# 44_GE_PORT_1-2.net
KiCad netlist of a schematic drawn in Altium Designer
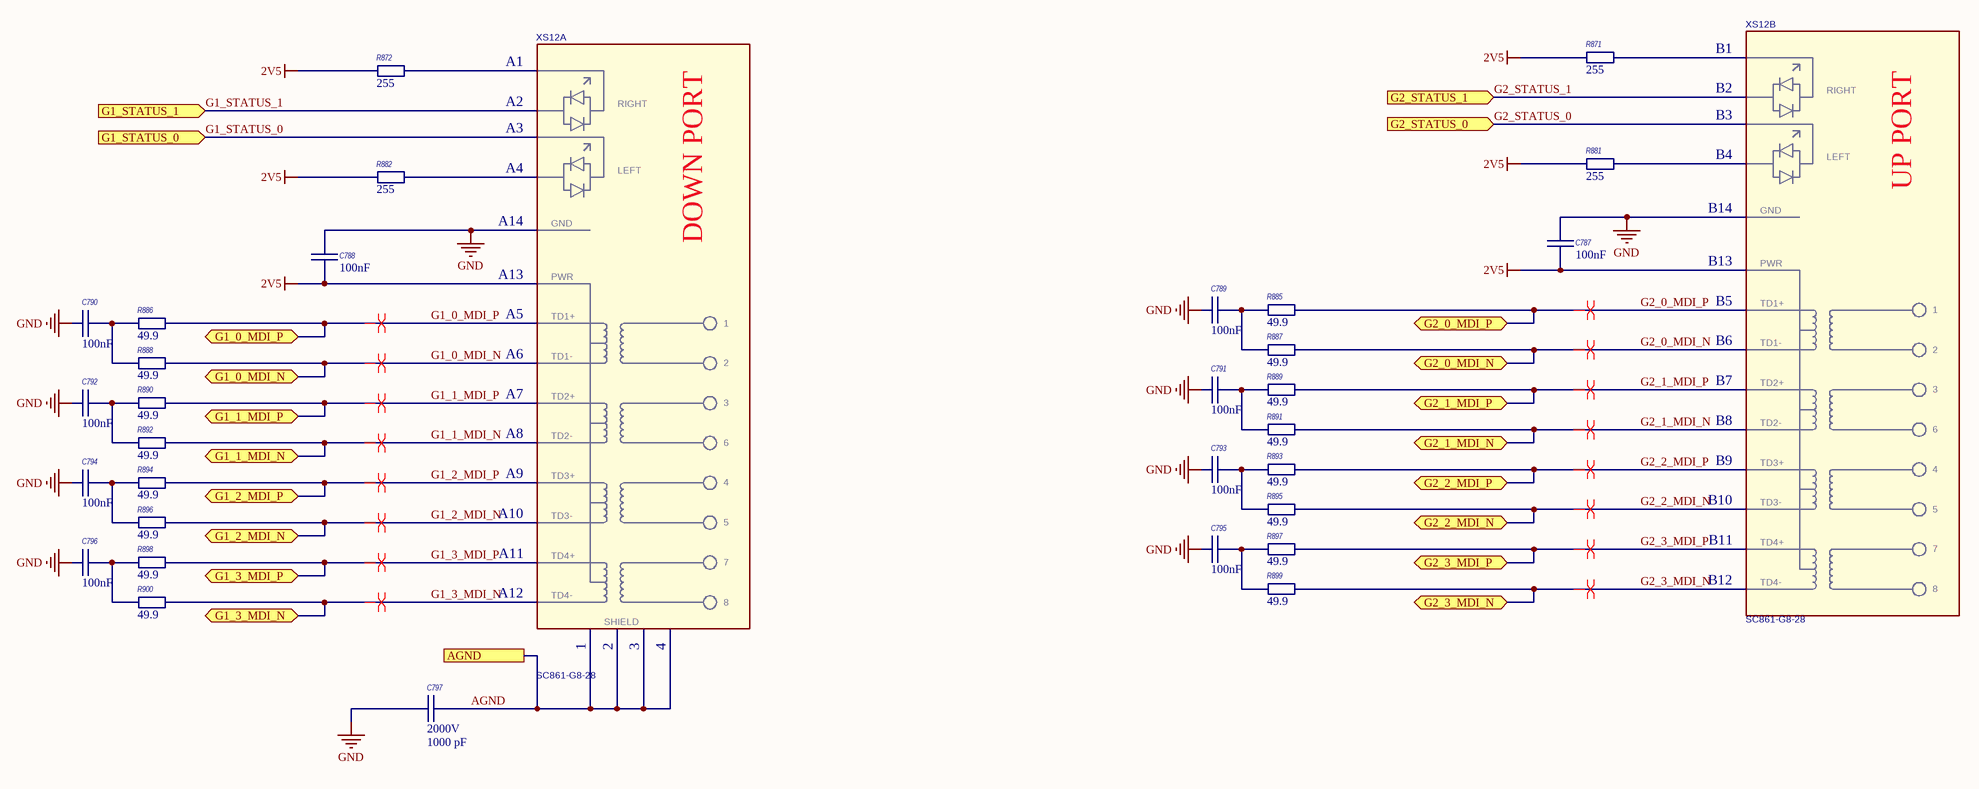
[diagram p0: 44_GE_PORT_1-2.SchDoc]

(export (version "E")
  (design (tool "Eeschema 10.0.6"))
  (components
    (comp (ref "C787")
      (value "GRM155R71E104KE14D")
      (footprint "C0402_IPC High Density")
      (description "C0402, 100nF, 25V, X7R")
      (fields
        (field (name "MANUFACTURER") "Murata")
        (field (name "CAPACITANCE") "100nF")
        (field (name "CUSTOMER PART NUMBER") "Конденсатор, 100n, 0402, 25V, X7R, 10%")
      )
      (libsource (lib "CAPACITORS") (part "GRM155R71E104KE14D"))
    )
    (comp (ref "C788")
      (value "GRM155R71E104KE14D")
      (footprint "C0402_IPC High Density")
      (description "C0402, 100nF, 25V, X7R")
      (fields
        (field (name "MANUFACTURER") "Murata")
        (field (name "CAPACITANCE") "100nF")
        (field (name "CUSTOMER PART NUMBER") "Конденсатор, 100n, 0402, 25V, X7R, 10%")
      )
      (libsource (lib "CAPACITORS") (part "GRM155R71E104KE14D"))
    )
    (comp (ref "C789")
      (value "GRM155R71E104KE14D")
      (footprint "C0402_IPC High Density")
      (description "C0402, 100nF, 25V, X7R")
      (fields
        (field (name "MANUFACTURER") "Murata")
        (field (name "CAPACITANCE") "100nF")
        (field (name "CUSTOMER PART NUMBER") "Конденсатор, 100n, 0402, 25V, X7R, 10%")
      )
      (libsource (lib "CAPACITORS") (part "GRM155R71E104KE14D"))
    )
    (comp (ref "C790")
      (value "GRM155R71E104KE14D")
      (footprint "C0402_IPC High Density")
      (description "C0402, 100nF, 25V, X7R")
      (fields
        (field (name "MANUFACTURER") "Murata")
        (field (name "CAPACITANCE") "100nF")
        (field (name "CUSTOMER PART NUMBER") "Конденсатор, 100n, 0402, 25V, X7R, 10%")
      )
      (libsource (lib "CAPACITORS") (part "GRM155R71E104KE14D"))
    )
    (comp (ref "C791")
      (value "GRM155R71E104KE14D")
      (footprint "C0402_IPC High Density")
      (description "C0402, 100nF, 25V, X7R")
      (fields
        (field (name "MANUFACTURER") "Murata")
        (field (name "CAPACITANCE") "100nF")
        (field (name "CUSTOMER PART NUMBER") "Конденсатор, 100n, 0402, 25V, X7R, 10%")
      )
      (libsource (lib "CAPACITORS") (part "GRM155R71E104KE14D"))
    )
    (comp (ref "C792")
      (value "GRM155R71E104KE14D")
      (footprint "C0402_IPC High Density")
      (description "C0402, 100nF, 25V, X7R")
      (fields
        (field (name "MANUFACTURER") "Murata")
        (field (name "CAPACITANCE") "100nF")
        (field (name "CUSTOMER PART NUMBER") "Конденсатор, 100n, 0402, 25V, X7R, 10%")
      )
      (libsource (lib "CAPACITORS") (part "GRM155R71E104KE14D"))
    )
    (comp (ref "C793")
      (value "GRM155R71E104KE14D")
      (footprint "C0402_IPC High Density")
      (description "C0402, 100nF, 25V, X7R")
      (fields
        (field (name "MANUFACTURER") "Murata")
        (field (name "CAPACITANCE") "100nF")
        (field (name "CUSTOMER PART NUMBER") "Конденсатор, 100n, 0402, 25V, X7R, 10%")
      )
      (libsource (lib "CAPACITORS") (part "GRM155R71E104KE14D"))
    )
    (comp (ref "C794")
      (value "GRM155R71E104KE14D")
      (footprint "C0402_IPC High Density")
      (description "C0402, 100nF, 25V, X7R")
      (fields
        (field (name "MANUFACTURER") "Murata")
        (field (name "CAPACITANCE") "100nF")
        (field (name "CUSTOMER PART NUMBER") "Конденсатор, 100n, 0402, 25V, X7R, 10%")
      )
      (libsource (lib "CAPACITORS") (part "GRM155R71E104KE14D"))
    )
    (comp (ref "C795")
      (value "GRM155R71E104KE14D")
      (footprint "C0402_IPC High Density")
      (description "C0402, 100nF, 25V, X7R")
      (fields
        (field (name "MANUFACTURER") "Murata")
        (field (name "CAPACITANCE") "100nF")
        (field (name "CUSTOMER PART NUMBER") "Конденсатор, 100n, 0402, 25V, X7R, 10%")
      )
      (libsource (lib "CAPACITORS") (part "GRM155R71E104KE14D"))
    )
    (comp (ref "C796")
      (value "GRM155R71E104KE14D")
      (footprint "C0402_IPC High Density")
      (description "C0402, 100nF, 25V, X7R")
      (fields
        (field (name "MANUFACTURER") "Murata")
        (field (name "CAPACITANCE") "100nF")
        (field (name "CUSTOMER PART NUMBER") "Конденсатор, 100n, 0402, 25V, X7R, 10%")
      )
      (libsource (lib "CAPACITORS") (part "GRM155R71E104KE14D"))
    )
    (comp (ref "C797")
      (value "GR442QR73D102KW01L")
      (footprint "C1808")
      (description "C1808, 2KV 1000pF, X7R")
      (fields
        (field (name "MANUFACTURER") "Murata")
        (field (name "TOLERANCE") "10 %")
        (field (name "VOLTAGE RATING") "2000V")
        (field (name "CAPACITANCE") "1000 pF")
      )
      (libsource (lib "CAPACITORS") (part "GR442QR73D102KW01L"))
    )
    (comp (ref "R871")
      (value "ERJ-2RKF2550X")
      (footprint "RESC1005[0402]")
      (description "R0402, 255R 1%")
      (fields
        (field (name "MANUFACTURER") "Panasonic")
        (field (name "TOLERANCE") "±1%")
        (field (name "RESISTANCE (OHMS)") "255")
      )
      (libsource (lib "RESISTOR") (part "ERJ-2RKF2550X"))
    )
    (comp (ref "R872")
      (value "ERJ-2RKF2550X")
      (footprint "RESC1005[0402]")
      (description "R0402, 255R 1%")
      (fields
        (field (name "MANUFACTURER") "Panasonic")
        (field (name "TOLERANCE") "±1%")
        (field (name "RESISTANCE (OHMS)") "255")
      )
      (libsource (lib "RESISTOR") (part "ERJ-2RKF2550X"))
    )
    (comp (ref "R881")
      (value "ERJ-2RKF2550X")
      (footprint "RESC1005[0402]")
      (description "R0402, 255R 1%")
      (fields
        (field (name "MANUFACTURER") "Panasonic")
        (field (name "TOLERANCE") "±1%")
        (field (name "RESISTANCE (OHMS)") "255")
      )
      (libsource (lib "RESISTOR") (part "ERJ-2RKF2550X"))
    )
    (comp (ref "R882")
      (value "ERJ-2RKF2550X")
      (footprint "RESC1005[0402]")
      (description "R0402, 255R 1%")
      (fields
        (field (name "MANUFACTURER") "Panasonic")
        (field (name "TOLERANCE") "±1%")
        (field (name "RESISTANCE (OHMS)") "255")
      )
      (libsource (lib "RESISTOR") (part "ERJ-2RKF2550X"))
    )
    (comp (ref "R885")
      (value "ERJ-2RKF49R9X")
      (footprint "R0402_IPC High Density")
      (description "R0402, 49.9R 1%")
      (fields
        (field (name "MANUFACTURER") "Panasonic")
        (field (name "TOLERANCE") "1 %")
        (field (name "RESISTANCE") "49.9")
      )
      (libsource (lib "RESISTOR") (part "ERJ-2RKF49R9X"))
    )
    (comp (ref "R886")
      (value "ERJ-2RKF49R9X")
      (footprint "R0402_IPC High Density")
      (description "R0402, 49.9R 1%")
      (fields
        (field (name "MANUFACTURER") "Panasonic")
        (field (name "TOLERANCE") "1 %")
        (field (name "RESISTANCE") "49.9")
      )
      (libsource (lib "RESISTOR") (part "ERJ-2RKF49R9X"))
    )
    (comp (ref "R887")
      (value "ERJ-2RKF49R9X")
      (footprint "R0402_IPC High Density")
      (description "R0402, 49.9R 1%")
      (fields
        (field (name "MANUFACTURER") "Panasonic")
        (field (name "TOLERANCE") "1 %")
        (field (name "RESISTANCE") "49.9")
      )
      (libsource (lib "RESISTOR") (part "ERJ-2RKF49R9X"))
    )
    (comp (ref "R888")
      (value "ERJ-2RKF49R9X")
      (footprint "R0402_IPC High Density")
      (description "R0402, 49.9R 1%")
      (fields
        (field (name "MANUFACTURER") "Panasonic")
        (field (name "TOLERANCE") "1 %")
        (field (name "RESISTANCE") "49.9")
      )
      (libsource (lib "RESISTOR") (part "ERJ-2RKF49R9X"))
    )
    (comp (ref "R889")
      (value "ERJ-2RKF49R9X")
      (footprint "R0402_IPC High Density")
      (description "R0402, 49.9R 1%")
      (fields
        (field (name "MANUFACTURER") "Panasonic")
        (field (name "TOLERANCE") "1 %")
        (field (name "RESISTANCE") "49.9")
      )
      (libsource (lib "RESISTOR") (part "ERJ-2RKF49R9X"))
    )
    (comp (ref "R890")
      (value "ERJ-2RKF49R9X")
      (footprint "R0402_IPC High Density")
      (description "R0402, 49.9R 1%")
      (fields
        (field (name "MANUFACTURER") "Panasonic")
        (field (name "TOLERANCE") "1 %")
        (field (name "RESISTANCE") "49.9")
      )
      (libsource (lib "RESISTOR") (part "ERJ-2RKF49R9X"))
    )
    (comp (ref "R891")
      (value "ERJ-2RKF49R9X")
      (footprint "R0402_IPC High Density")
      (description "R0402, 49.9R 1%")
      (fields
        (field (name "MANUFACTURER") "Panasonic")
        (field (name "TOLERANCE") "1 %")
        (field (name "RESISTANCE") "49.9")
      )
      (libsource (lib "RESISTOR") (part "ERJ-2RKF49R9X"))
    )
    (comp (ref "R892")
      (value "ERJ-2RKF49R9X")
      (footprint "R0402_IPC High Density")
      (description "R0402, 49.9R 1%")
      (fields
        (field (name "MANUFACTURER") "Panasonic")
        (field (name "TOLERANCE") "1 %")
        (field (name "RESISTANCE") "49.9")
      )
      (libsource (lib "RESISTOR") (part "ERJ-2RKF49R9X"))
    )
    (comp (ref "R893")
      (value "ERJ-2RKF49R9X")
      (footprint "R0402_IPC High Density")
      (description "R0402, 49.9R 1%")
      (fields
        (field (name "MANUFACTURER") "Panasonic")
        (field (name "TOLERANCE") "1 %")
        (field (name "RESISTANCE") "49.9")
      )
      (libsource (lib "RESISTOR") (part "ERJ-2RKF49R9X"))
    )
    (comp (ref "R894")
      (value "ERJ-2RKF49R9X")
      (footprint "R0402_IPC High Density")
      (description "R0402, 49.9R 1%")
      (fields
        (field (name "MANUFACTURER") "Panasonic")
        (field (name "TOLERANCE") "1 %")
        (field (name "RESISTANCE") "49.9")
      )
      (libsource (lib "RESISTOR") (part "ERJ-2RKF49R9X"))
    )
    (comp (ref "R895")
      (value "ERJ-2RKF49R9X")
      (footprint "R0402_IPC High Density")
      (description "R0402, 49.9R 1%")
      (fields
        (field (name "MANUFACTURER") "Panasonic")
        (field (name "TOLERANCE") "1 %")
        (field (name "RESISTANCE") "49.9")
      )
      (libsource (lib "RESISTOR") (part "ERJ-2RKF49R9X"))
    )
    (comp (ref "R896")
      (value "ERJ-2RKF49R9X")
      (footprint "R0402_IPC High Density")
      (description "R0402, 49.9R 1%")
      (fields
        (field (name "MANUFACTURER") "Panasonic")
        (field (name "TOLERANCE") "1 %")
        (field (name "RESISTANCE") "49.9")
      )
      (libsource (lib "RESISTOR") (part "ERJ-2RKF49R9X"))
    )
    (comp (ref "R897")
      (value "ERJ-2RKF49R9X")
      (footprint "R0402_IPC High Density")
      (description "R0402, 49.9R 1%")
      (fields
        (field (name "MANUFACTURER") "Panasonic")
        (field (name "TOLERANCE") "1 %")
        (field (name "RESISTANCE") "49.9")
      )
      (libsource (lib "RESISTOR") (part "ERJ-2RKF49R9X"))
    )
    (comp (ref "R898")
      (value "ERJ-2RKF49R9X")
      (footprint "R0402_IPC High Density")
      (description "R0402, 49.9R 1%")
      (fields
        (field (name "MANUFACTURER") "Panasonic")
        (field (name "TOLERANCE") "1 %")
        (field (name "RESISTANCE") "49.9")
      )
      (libsource (lib "RESISTOR") (part "ERJ-2RKF49R9X"))
    )
    (comp (ref "R899")
      (value "ERJ-2RKF49R9X")
      (footprint "R0402_IPC High Density")
      (description "R0402, 49.9R 1%")
      (fields
        (field (name "MANUFACTURER") "Panasonic")
        (field (name "TOLERANCE") "1 %")
        (field (name "RESISTANCE") "49.9")
      )
      (libsource (lib "RESISTOR") (part "ERJ-2RKF49R9X"))
    )
    (comp (ref "R900")
      (value "ERJ-2RKF49R9X")
      (footprint "R0402_IPC High Density")
      (description "R0402, 49.9R 1%")
      (fields
        (field (name "MANUFACTURER") "Panasonic")
        (field (name "TOLERANCE") "1 %")
        (field (name "RESISTANCE") "49.9")
      )
      (libsource (lib "RESISTOR") (part "ERJ-2RKF49R9X"))
    )
    (comp (ref "XS12")
      (value "SC861-G8-28")
      (footprint "SC861-G8-28")
      (description "Connector RJ45 1G 2 ports (2*1) and LED")
      (fields
        (field (name "CUSTOMER PART NUMBER") "Разъем, SC861-G8-28, Connector RJ45 1G 2 ports (2*1) and LED")
        (field (name "MANUFACTURER") "Yueqing Shichuang Electronics")
      )
      (libsource (lib "CONNECTORS") (part "SC861-G8-28"))
    )
  )
  (nets
    (net (code "1") (name "/AGND") (class "Default")
      (node (ref "C797") (pin "2") (pintype "passive"))
      (node (ref "XS12") (pin "1") (pintype "passive"))
      (node (ref "XS12") (pin "2") (pintype "passive"))
      (node (ref "XS12") (pin "3") (pintype "passive"))
      (node (ref "XS12") (pin "4") (pintype "passive"))
    )
    (net (code "2") (name "/G1_0_MDI_N") (class "Default")
      (node (ref "R888") (pin "2") (pintype "passive"))
      (node (ref "XS12") (pin "A6") (pintype "passive"))
    )
    (net (code "3") (name "/G1_0_MDI_P") (class "Default")
      (node (ref "R886") (pin "2") (pintype "passive"))
      (node (ref "XS12") (pin "A5") (pintype "passive"))
    )
    (net (code "4") (name "/G1_1_MDI_N") (class "Default")
      (node (ref "R892") (pin "2") (pintype "passive"))
      (node (ref "XS12") (pin "A8") (pintype "passive"))
    )
    (net (code "5") (name "/G1_1_MDI_P") (class "Default")
      (node (ref "R890") (pin "2") (pintype "passive"))
      (node (ref "XS12") (pin "A7") (pintype "passive"))
    )
    (net (code "6") (name "/G1_2_MDI_N") (class "Default")
      (node (ref "R896") (pin "2") (pintype "passive"))
      (node (ref "XS12") (pin "A10") (pintype "passive"))
    )
    (net (code "7") (name "/G1_2_MDI_P") (class "Default")
      (node (ref "R894") (pin "2") (pintype "passive"))
      (node (ref "XS12") (pin "A9") (pintype "passive"))
    )
    (net (code "8") (name "/G1_3_MDI_N") (class "Default")
      (node (ref "R900") (pin "2") (pintype "passive"))
      (node (ref "XS12") (pin "A12") (pintype "passive"))
    )
    (net (code "9") (name "/G1_3_MDI_P") (class "Default")
      (node (ref "R898") (pin "2") (pintype "passive"))
      (node (ref "XS12") (pin "A11") (pintype "passive"))
    )
    (net (code "10") (name "/G1_STATUS_0") (class "Default")
      (node (ref "XS12") (pin "A3") (pintype "passive"))
    )
    (net (code "11") (name "/G1_STATUS_1") (class "Default")
      (node (ref "XS12") (pin "A2") (pintype "passive"))
    )
    (net (code "12") (name "/G2_0_MDI_N") (class "Default")
      (node (ref "R887") (pin "2") (pintype "passive"))
      (node (ref "XS12") (pin "B6") (pintype "passive"))
    )
    (net (code "13") (name "/G2_0_MDI_P") (class "Default")
      (node (ref "R885") (pin "2") (pintype "passive"))
      (node (ref "XS12") (pin "B5") (pintype "passive"))
    )
    (net (code "14") (name "/G2_1_MDI_N") (class "Default")
      (node (ref "R891") (pin "2") (pintype "passive"))
      (node (ref "XS12") (pin "B8") (pintype "passive"))
    )
    (net (code "15") (name "/G2_1_MDI_P") (class "Default")
      (node (ref "R889") (pin "2") (pintype "passive"))
      (node (ref "XS12") (pin "B7") (pintype "passive"))
    )
    (net (code "16") (name "/G2_2_MDI_N") (class "Default")
      (node (ref "R895") (pin "2") (pintype "passive"))
      (node (ref "XS12") (pin "B10") (pintype "passive"))
    )
    (net (code "17") (name "/G2_2_MDI_P") (class "Default")
      (node (ref "R893") (pin "2") (pintype "passive"))
      (node (ref "XS12") (pin "B9") (pintype "passive"))
    )
    (net (code "18") (name "/G2_3_MDI_N") (class "Default")
      (node (ref "R899") (pin "2") (pintype "passive"))
      (node (ref "XS12") (pin "B12") (pintype "passive"))
    )
    (net (code "19") (name "/G2_3_MDI_P") (class "Default")
      (node (ref "R897") (pin "2") (pintype "passive"))
      (node (ref "XS12") (pin "B11") (pintype "passive"))
    )
    (net (code "20") (name "/G2_STATUS_0") (class "Default")
      (node (ref "XS12") (pin "B3") (pintype "passive"))
    )
    (net (code "21") (name "/G2_STATUS_1") (class "Default")
      (node (ref "XS12") (pin "B2") (pintype "passive"))
    )
    (net (code "22") (name "2V5") (class "Default")
      (node (ref "C787") (pin "2") (pintype "passive"))
      (node (ref "C788") (pin "2") (pintype "passive"))
      (node (ref "R871") (pin "1") (pintype "passive"))
      (node (ref "R872") (pin "1") (pintype "passive"))
      (node (ref "R881") (pin "1") (pintype "passive"))
      (node (ref "R882") (pin "1") (pintype "passive"))
      (node (ref "XS12") (pin "A13") (pintype "passive"))
      (node (ref "XS12") (pin "B13") (pintype "passive"))
    )
    (net (code "23") (name "GND") (class "Default")
      (node (ref "C787") (pin "1") (pintype "passive"))
      (node (ref "C788") (pin "1") (pintype "passive"))
      (node (ref "C789") (pin "1") (pintype "passive"))
      (node (ref "C790") (pin "1") (pintype "passive"))
      (node (ref "C791") (pin "1") (pintype "passive"))
      (node (ref "C792") (pin "1") (pintype "passive"))
      (node (ref "C793") (pin "1") (pintype "passive"))
      (node (ref "C794") (pin "1") (pintype "passive"))
      (node (ref "C795") (pin "1") (pintype "passive"))
      (node (ref "C796") (pin "1") (pintype "passive"))
      (node (ref "C797") (pin "1") (pintype "passive"))
      (node (ref "XS12") (pin "A14") (pintype "passive"))
      (node (ref "XS12") (pin "B14") (pintype "passive"))
    )
    (net (code "24") (name "Net-(C789-Pad2)") (class "Default")
      (node (ref "C789") (pin "2") (pintype "passive"))
      (node (ref "R885") (pin "1") (pintype "passive"))
      (node (ref "R887") (pin "1") (pintype "passive"))
    )
    (net (code "25") (name "Net-(C790-Pad2)") (class "Default")
      (node (ref "C790") (pin "2") (pintype "passive"))
      (node (ref "R886") (pin "1") (pintype "passive"))
      (node (ref "R888") (pin "1") (pintype "passive"))
    )
    (net (code "26") (name "Net-(C791-Pad2)") (class "Default")
      (node (ref "C791") (pin "2") (pintype "passive"))
      (node (ref "R889") (pin "1") (pintype "passive"))
      (node (ref "R891") (pin "1") (pintype "passive"))
    )
    (net (code "27") (name "Net-(C792-Pad2)") (class "Default")
      (node (ref "C792") (pin "2") (pintype "passive"))
      (node (ref "R890") (pin "1") (pintype "passive"))
      (node (ref "R892") (pin "1") (pintype "passive"))
    )
    (net (code "28") (name "Net-(C793-Pad2)") (class "Default")
      (node (ref "C793") (pin "2") (pintype "passive"))
      (node (ref "R893") (pin "1") (pintype "passive"))
      (node (ref "R895") (pin "1") (pintype "passive"))
    )
    (net (code "29") (name "Net-(C794-Pad2)") (class "Default")
      (node (ref "C794") (pin "2") (pintype "passive"))
      (node (ref "R894") (pin "1") (pintype "passive"))
      (node (ref "R896") (pin "1") (pintype "passive"))
    )
    (net (code "30") (name "Net-(C795-Pad2)") (class "Default")
      (node (ref "C795") (pin "2") (pintype "passive"))
      (node (ref "R897") (pin "1") (pintype "passive"))
      (node (ref "R899") (pin "1") (pintype "passive"))
    )
    (net (code "31") (name "Net-(C796-Pad2)") (class "Default")
      (node (ref "C796") (pin "2") (pintype "passive"))
      (node (ref "R898") (pin "1") (pintype "passive"))
      (node (ref "R900") (pin "1") (pintype "passive"))
    )
    (net (code "32") (name "Net-(R871-Pad2)") (class "Default")
      (node (ref "R871") (pin "2") (pintype "passive"))
      (node (ref "XS12") (pin "B1") (pintype "passive"))
    )
    (net (code "33") (name "Net-(R872-Pad2)") (class "Default")
      (node (ref "R872") (pin "2") (pintype "passive"))
      (node (ref "XS12") (pin "A1") (pintype "passive"))
    )
    (net (code "34") (name "Net-(R881-Pad2)") (class "Default")
      (node (ref "R881") (pin "2") (pintype "passive"))
      (node (ref "XS12") (pin "B4") (pintype "passive"))
    )
    (net (code "35") (name "Net-(R882-Pad2)") (class "Default")
      (node (ref "R882") (pin "2") (pintype "passive"))
      (node (ref "XS12") (pin "A4") (pintype "passive"))
    )
    (net (code "36") (name "unconnected-(XS12-Pad113)") (class "Default")
      (node (ref "XS12") (pin "113") (pintype "passive"))
    )
    (net (code "37") (name "unconnected-(XS12-Pad113)_1") (class "Default")
      (node (ref "XS12") (pin "113") (pintype "passive"))
    )
    (net (code "38") (name "unconnected-(XS12-Pad114)") (class "Default")
      (node (ref "XS12") (pin "114") (pintype "passive"))
    )
    (net (code "39") (name "unconnected-(XS12-Pad114)_1") (class "Default")
      (node (ref "XS12") (pin "114") (pintype "passive"))
    )
    (net (code "40") (name "unconnected-(XS12-Pad115)") (class "Default")
      (node (ref "XS12") (pin "115") (pintype "passive"))
    )
    (net (code "41") (name "unconnected-(XS12-Pad115)_1") (class "Default")
      (node (ref "XS12") (pin "115") (pintype "passive"))
    )
    (net (code "42") (name "unconnected-(XS12-Pad116)") (class "Default")
      (node (ref "XS12") (pin "116") (pintype "passive"))
    )
    (net (code "43") (name "unconnected-(XS12-Pad116)_1") (class "Default")
      (node (ref "XS12") (pin "116") (pintype "passive"))
    )
    (net (code "44") (name "unconnected-(XS12-Pad117)") (class "Default")
      (node (ref "XS12") (pin "117") (pintype "passive"))
    )
    (net (code "45") (name "unconnected-(XS12-Pad117)_1") (class "Default")
      (node (ref "XS12") (pin "117") (pintype "passive"))
    )
    (net (code "46") (name "unconnected-(XS12-Pad118)") (class "Default")
      (node (ref "XS12") (pin "118") (pintype "passive"))
    )
    (net (code "47") (name "unconnected-(XS12-Pad118)_1") (class "Default")
      (node (ref "XS12") (pin "118") (pintype "passive"))
    )
    (net (code "48") (name "unconnected-(XS12-Pad119)") (class "Default")
      (node (ref "XS12") (pin "119") (pintype "passive"))
    )
    (net (code "49") (name "unconnected-(XS12-Pad119)_1") (class "Default")
      (node (ref "XS12") (pin "119") (pintype "passive"))
    )
    (net (code "50") (name "unconnected-(XS12-Pad120)") (class "Default")
      (node (ref "XS12") (pin "120") (pintype "passive"))
    )
    (net (code "51") (name "unconnected-(XS12-Pad120)_1") (class "Default")
      (node (ref "XS12") (pin "120") (pintype "passive"))
    )
    (net (code "52") (name "unconnected-(XS12-Pad121)") (class "Default")
      (node (ref "XS12") (pin "121") (pintype "passive"))
    )
    (net (code "53") (name "unconnected-(XS12-Pad121)_1") (class "Default")
      (node (ref "XS12") (pin "121") (pintype "passive"))
    )
  )
)
